# WireTest.net
KiCad netlist of a schematic drawn in Altium Designer
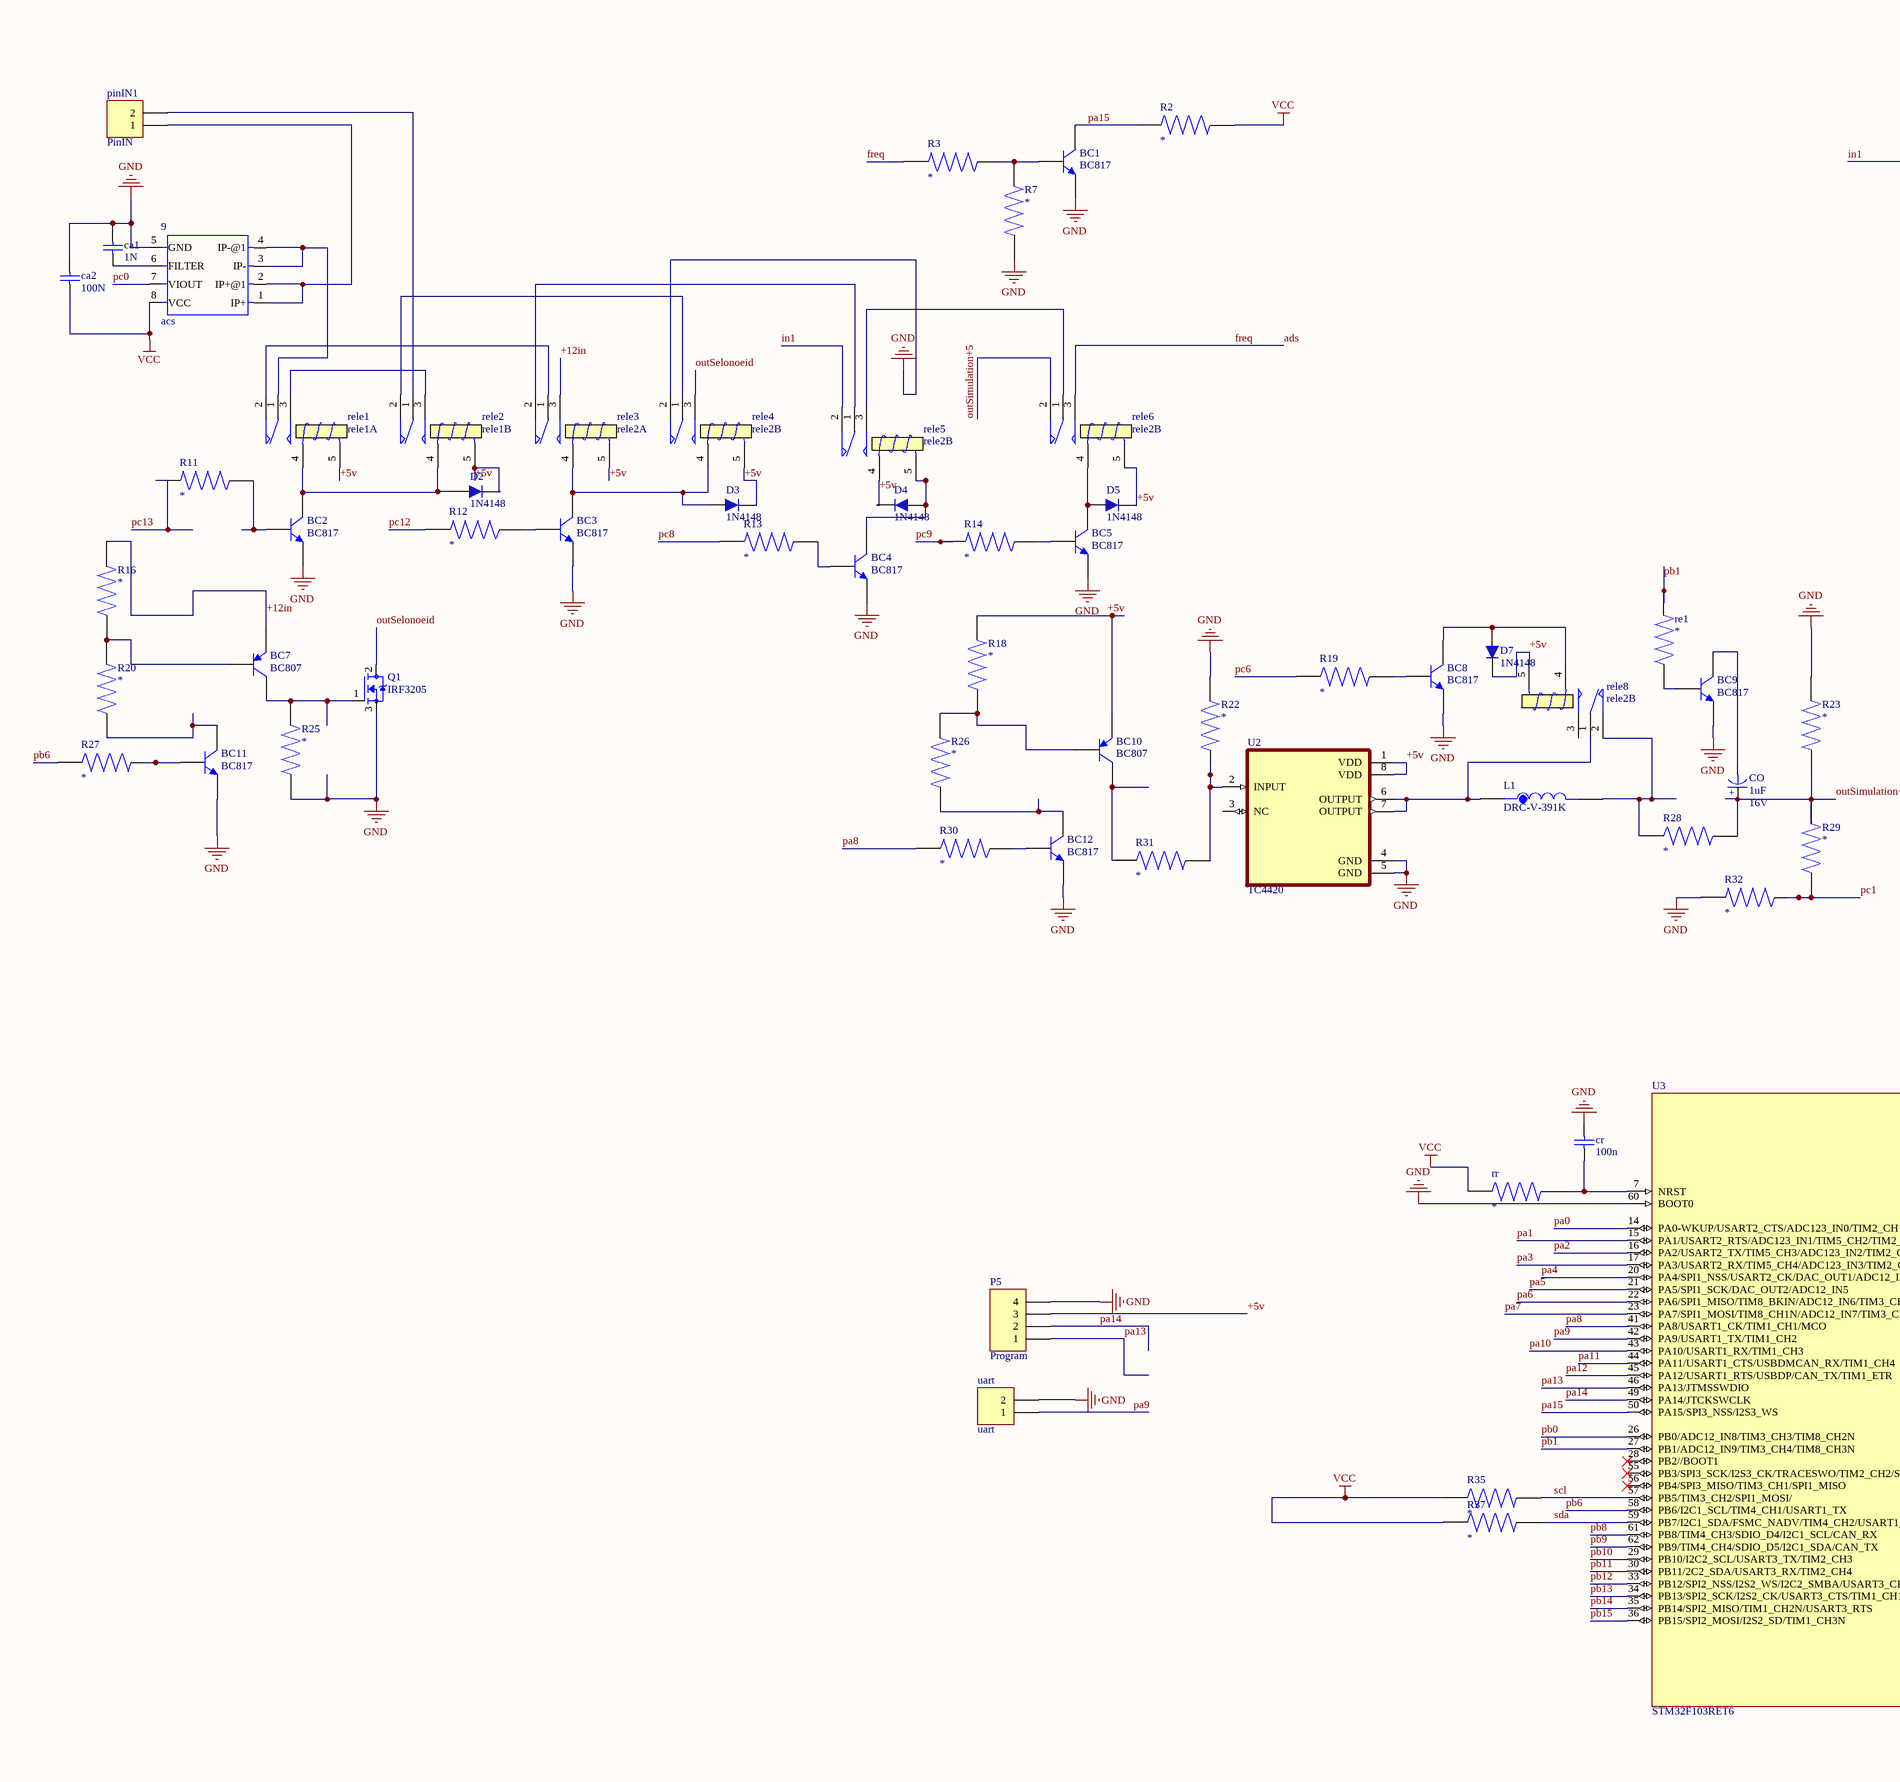
[diagram p0: WireTest.SchDoc, left]
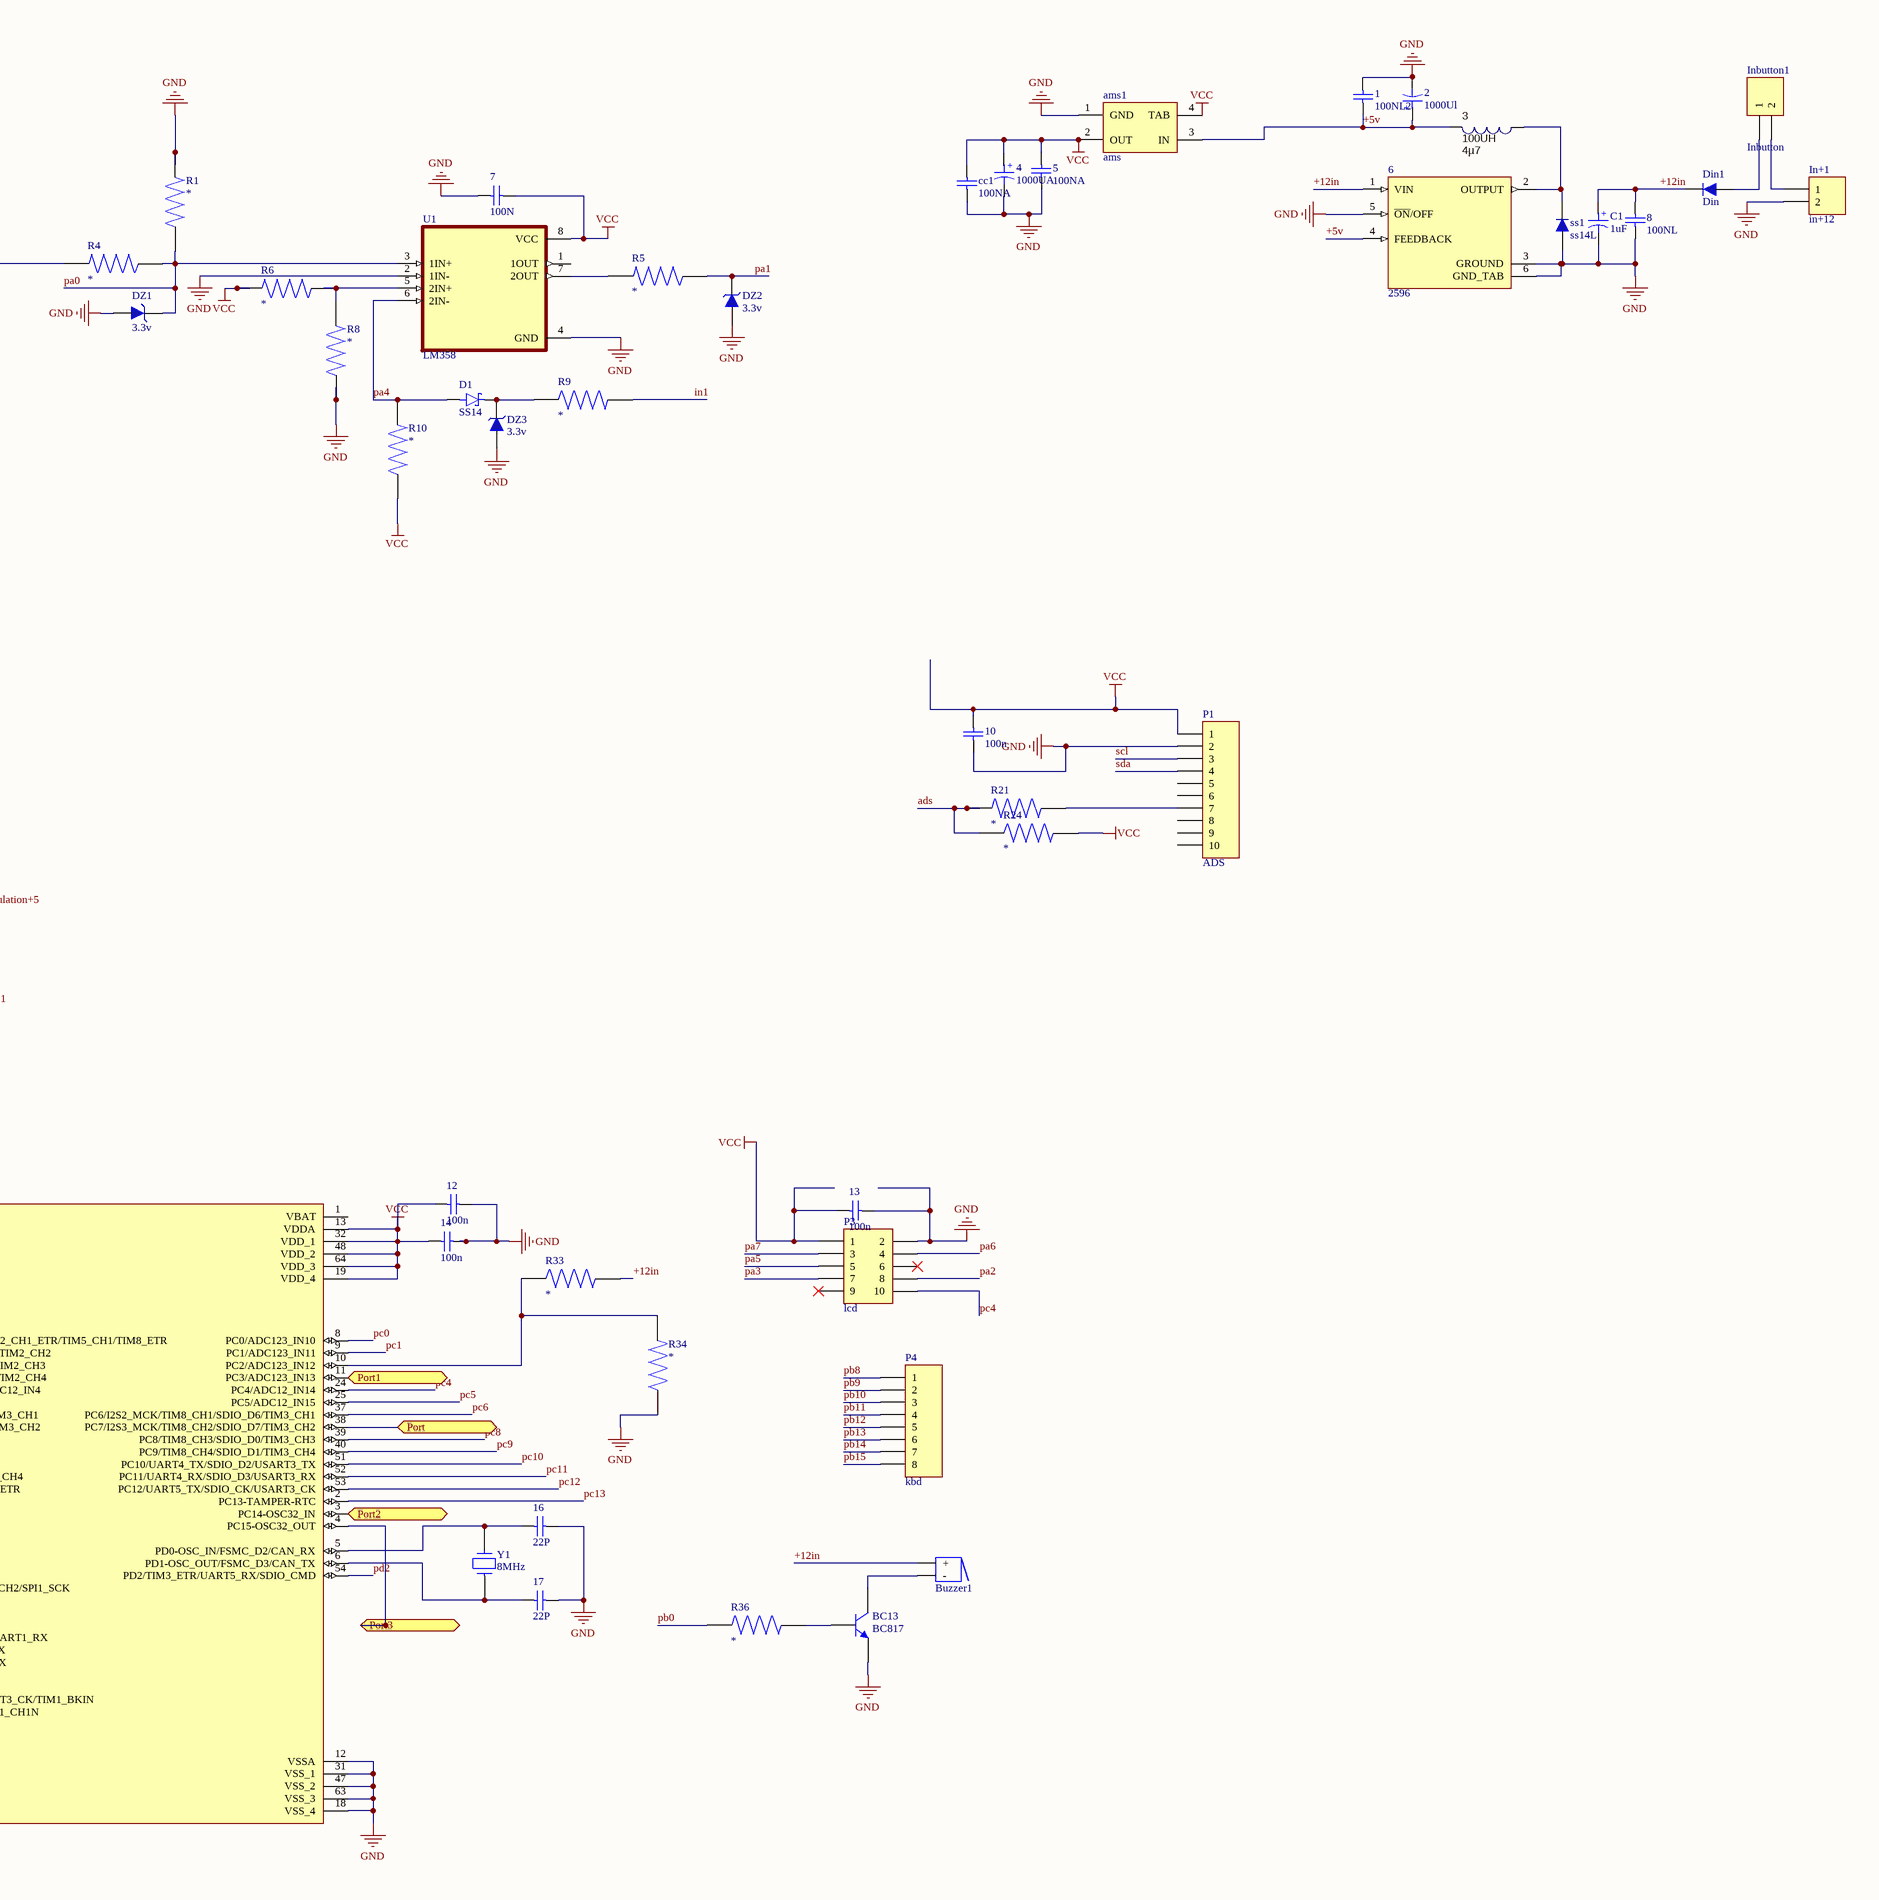
[diagram p1: WireTest.SchDoc, right]

(export (version "E")
  (design (tool "Eeschema 10.0.6"))
  (components
    (comp (ref "1")
      (value "100NL2")
      (footprint "CAPC3413X12N")
      (description "CAP 0805")
      (fields (field (name "DESIGNER") "Abbas Basereh"))
      (libsource (lib "Altium") (part "CAP SMD 0805"))
    )
    (comp (ref "2")
      (value "1000Ul")
      (footprint "Cap electrolitic radial 8x12-3.5")
      (description "Cap electrolitic radial")
      (fields (field (name "DESIGNER") "Abbas Basereh"))
      (libsource (lib "Altium") (part "Cap ELECTROLITIC TOTAL SIZE"))
    )
    (comp (ref "3")
      (value "100UH")
      (footprint "Inductor SMD 3x3.2mm")
      (description "Inductor 4.7µH SMD 3x3.2mm")
      (fields (field (name "TOLERANCE") "±20%") (field (name "ALTIUM_VALUE") "4µ7"))
      (libsource (lib "Altium") (part "Inductor 4.7µH SMD 3x3.2mm"))
    )
    (comp (ref "4")
      (value "1000UA")
      (footprint "Cap electrolitic radial 8x12-3.5")
      (description "Cap electrolitic radial")
      (fields (field (name "DESIGNER") "Abbas Basereh"))
      (libsource (lib "Altium") (part "Cap ELECTROLITIC TOTAL SIZE"))
    )
    (comp (ref "5")
      (value "100NA")
      (footprint "CAPC3413X12N")
      (description "CAP 0805")
      (fields (field (name "DESIGNER") "Abbas Basereh"))
      (libsource (lib "Altium") (part "CAP SMD 0805"))
    )
    (comp (ref "6")
      (value "2596")
      (footprint "LM2596S-5.0:TO170P1524X483-6N")
      (fields (field (name "MP") "LM2596S-5.0"))
      (libsource (lib "LM2596S-5.0") (part "LM2596S-5.0"))
    )
    (comp (ref "7")
      (value "100N")
      (footprint "CAPC3413X12N")
      (description "CAP 0805")
      (fields (field (name "DESIGNER") "Abbas Basereh"))
      (libsource (lib "Altium") (part "CAP SMD 0805"))
    )
    (comp (ref "8")
      (value "100NL")
      (footprint "CAPC3413X12N")
      (description "CAP 0805")
      (fields (field (name "DESIGNER") "Abbas Basereh"))
      (libsource (lib "Altium") (part "CAP SMD 0805"))
    )
    (comp (ref "9")
      (value "acs")
      (footprint "SOIC8-1.27-5X4MM")
      (description "Current Sensor 5A 1 Channel Hall Effect, Open Loop Bidirectional 8-SOIC _0.154, 3.90mm Width_")
      (fields (field (name "MF") "Allegro") (field (name "MP") "ACS712ELCTR-05B-T"))
      (libsource (lib "CURRENT-ACS712ELCTR-05B-T_SOIC8-5X4MM_") (part "CURRENT-ACS712ELCTR-05B-T(SOIC8-5X4MM)"))
    )
    (comp (ref "10")
      (value "100n")
      (footprint "CAPC3413X12N")
      (description "CAP 0805")
      (fields (field (name "DESIGNER") "Abbas Basereh"))
      (libsource (lib "Altium") (part "CAP SMD 0805"))
    )
    (comp (ref "12")
      (value "100n")
      (footprint "CAPC3413X12N")
      (description "CAP 0805")
      (fields (field (name "DESIGNER") "Abbas Basereh"))
      (libsource (lib "Altium") (part "CAP SMD 0805"))
    )
    (comp (ref "13")
      (value "100n")
      (footprint "CAPC3413X12N")
      (description "CAP 0805")
      (fields (field (name "DESIGNER") "Abbas Basereh"))
      (libsource (lib "Altium") (part "CAP SMD 0805"))
    )
    (comp (ref "14")
      (value "100n")
      (footprint "CAPC3413X12N")
      (description "CAP 0805")
      (fields (field (name "DESIGNER") "Abbas Basereh"))
      (libsource (lib "Altium") (part "CAP SMD 0805"))
    )
    (comp (ref "16")
      (value "22P")
      (footprint "CAPC3413X12N")
      (description "CAP 0805")
      (fields (field (name "DESIGNER") "Abbas Basereh"))
      (libsource (lib "Altium") (part "CAP SMD 0805"))
    )
    (comp (ref "17")
      (value "22P")
      (footprint "CAPC3413X12N")
      (description "CAP 0805")
      (fields (field (name "DESIGNER") "Abbas Basereh"))
      (libsource (lib "Altium") (part "CAP SMD 0805"))
    )
    (comp (ref "ams1")
      (value "ams")
      (footprint "MP04A_N")
      (description "x.x Volt, 800mA Low-Dropout Linear Regulator, 4-pin SOT-223")
      (fields
        (field (name "PARTNUMBER") "LM1117IMP-3.3")
        (field (name "MANUFACTURER") "National Semiconductor")
        (field (name "PUBLISHER") "Altium Limited")
      )
      (libsource (lib "My_Library") (part "LM1117IMP-x.x"))
    )
    (comp (ref "BC1")
      (value "BC817")
      (footprint "SOT23_N")
      (description "45 V, 500 mA NPN general-purpose transistors")
      (fields (field (name "PUBLISHER") "Abbas Basereh"))
      (libsource (lib "Altium") (part "BC817"))
    )
    (comp (ref "BC2")
      (value "BC817")
      (footprint "SOT23_N")
      (description "45 V, 500 mA NPN general-purpose transistors")
      (fields (field (name "PUBLISHER") "Abbas Basereh"))
      (libsource (lib "Altium") (part "BC817"))
    )
    (comp (ref "BC3")
      (value "BC817")
      (footprint "SOT23_N")
      (description "45 V, 500 mA NPN general-purpose transistors")
      (fields (field (name "PUBLISHER") "Abbas Basereh"))
      (libsource (lib "Altium") (part "BC817"))
    )
    (comp (ref "BC4")
      (value "BC817")
      (footprint "SOT23_N")
      (description "45 V, 500 mA NPN general-purpose transistors")
      (fields (field (name "PUBLISHER") "Abbas Basereh"))
      (libsource (lib "Altium") (part "BC817"))
    )
    (comp (ref "BC5")
      (value "BC817")
      (footprint "SOT23_N")
      (description "45 V, 500 mA NPN general-purpose transistors")
      (fields (field (name "PUBLISHER") "Abbas Basereh"))
      (libsource (lib "Altium") (part "BC817"))
    )
    (comp (ref "BC7")
      (value "BC807")
      (footprint "SOT23_BEC_N")
      (description "PNP General-purpose Transistor")
      (fields (field (name "PUBLISHER") "Altium Limited"))
      (libsource (lib "Altium") (part "BC807"))
    )
    (comp (ref "BC8")
      (value "BC817")
      (footprint "SOT23_N")
      (description "45 V, 500 mA NPN general-purpose transistors")
      (fields (field (name "PUBLISHER") "Abbas Basereh"))
      (libsource (lib "Altium") (part "BC817"))
    )
    (comp (ref "BC9")
      (value "BC817")
      (footprint "SOT23_N")
      (description "45 V, 500 mA NPN general-purpose transistors")
      (fields (field (name "PUBLISHER") "Abbas Basereh"))
      (libsource (lib "Altium") (part "BC817"))
    )
    (comp (ref "BC10")
      (value "BC807")
      (footprint "SOT23_BEC_N")
      (description "PNP General-purpose Transistor")
      (fields (field (name "PUBLISHER") "Altium Limited"))
      (libsource (lib "Altium") (part "BC807"))
    )
    (comp (ref "BC11")
      (value "BC817")
      (footprint "SOT23_N")
      (description "45 V, 500 mA NPN general-purpose transistors")
      (fields (field (name "PUBLISHER") "Abbas Basereh"))
      (libsource (lib "Altium") (part "BC817"))
    )
    (comp (ref "BC12")
      (value "BC817")
      (footprint "SOT23_N")
      (description "45 V, 500 mA NPN general-purpose transistors")
      (fields (field (name "PUBLISHER") "Abbas Basereh"))
      (libsource (lib "Altium") (part "BC817"))
    )
    (comp (ref "BC13")
      (value "BC817")
      (footprint "SOT23_N")
      (description "45 V, 500 mA NPN general-purpose transistors")
      (fields (field (name "PUBLISHER") "Abbas Basereh"))
      (libsource (lib "Altium") (part "BC817"))
    )
    (comp (ref "Buzzer1")
      (value "Buzzer")
      (footprint "BUZZER")
      (fields (field (name "DESIGNER") "Seyed Mohsen Ghasemain"))
      (libsource (lib "usefully_Library") (part "Buzzer"))
    )
    (comp (ref "C1")
      (value "1uF")
      (footprint "Cap electrolitic radial 8x12-3.5")
      (description "Cap electrolitic radial")
      (fields (field (name "DESIGNER") "Abbas Basereh"))
      (libsource (lib "Altium") (part "Cap ELECTROLITIC TOTAL SIZE"))
    )
    (comp (ref "ca1")
      (value "1N")
      (footprint "CAPC3413X12N")
      (description "CAP 0805")
      (fields (field (name "DESIGNER") "Abbas Basereh"))
      (libsource (lib "Altium") (part "CAP SMD 0805"))
    )
    (comp (ref "ca2")
      (value "100N")
      (footprint "CAPC3413X12N")
      (description "CAP 0805")
      (fields (field (name "DESIGNER") "Abbas Basereh"))
      (libsource (lib "Altium") (part "CAP SMD 0805"))
    )
    (comp (ref "cc1")
      (value "100NA")
      (footprint "CAPC3413X12N")
      (description "CAP 0805")
      (fields (field (name "DESIGNER") "Abbas Basereh"))
      (libsource (lib "Altium") (part "CAP SMD 0805"))
    )
    (comp (ref "CO")
      (value "1uF")
      (footprint "cap 01")
      (description "Polar Capacitor")
      (fields
        (field (name "VOLTAGE") "16V")
        (field (name "Comment") "400U")
        (field (name "DESIGNER") "Saeid Jorablo")
      )
      (libsource (lib "My_Library") (part "Cap-Polar"))
    )
    (comp (ref "cr")
      (value "100n")
      (footprint "CAPC3413X12N")
      (description "CAP 0805")
      (fields (field (name "DESIGNER") "Abbas Basereh"))
      (libsource (lib "Altium") (part "CAP SMD 0805"))
    )
    (comp (ref "D1") (value "SS14") (footprint "DIOM4325X250N") (libsource (lib "SS14") (part "SS14")))
    (comp (ref "D2")
      (value "1N4148")
      (footprint "Diode 1n4148 SMD")
      (description "General Semicoductor")
      (libsource (lib "Altium") (part "1N4148 SMD"))
    )
    (comp (ref "D3")
      (value "1N4148")
      (footprint "Diode 1n4148 SMD")
      (description "General Semicoductor")
      (libsource (lib "Altium") (part "1N4148 SMD"))
    )
    (comp (ref "D4")
      (value "1N4148")
      (footprint "Diode 1n4148 SMD")
      (description "General Semicoductor")
      (libsource (lib "Altium") (part "1N4148 SMD"))
    )
    (comp (ref "D5")
      (value "1N4148")
      (footprint "Diode 1n4148 SMD")
      (description "General Semicoductor")
      (libsource (lib "Altium") (part "1N4148 SMD"))
    )
    (comp (ref "D7")
      (value "1N4148")
      (footprint "Diode 1n4148 SMD")
      (description "General Semicoductor")
      (libsource (lib "Altium") (part "1N4148 SMD"))
    )
    (comp (ref "Din1")
      (value "Din")
      (footprint "Diode 1W Stand")
      (description "Diode DIP Package")
      (fields (field (name "PUBLISHER") "Altium Limited"))
      (libsource (lib "Altium") (part "Diode DIP Package"))
    )
    (comp (ref "DZ1")
      (value "3.3v")
      (footprint "SOD80, LL-34")
      (description "DIODE ZENER GENERAL")
      (fields (field (name "PUBLISHER") "Abbas Basereh"))
      (libsource (lib "Altium") (part "ZENER GENERAL DIODE"))
    )
    (comp (ref "DZ2")
      (value "3.3v")
      (footprint "SOD80, LL-34")
      (description "DIODE ZENER GENERAL")
      (fields (field (name "PUBLISHER") "Abbas Basereh"))
      (libsource (lib "Altium") (part "ZENER GENERAL DIODE"))
    )
    (comp (ref "DZ3")
      (value "3.3v")
      (footprint "SOD80, LL-34")
      (description "DIODE ZENER GENERAL")
      (fields (field (name "PUBLISHER") "Abbas Basereh"))
      (libsource (lib "Altium") (part "ZENER GENERAL DIODE"))
    )
    (comp (ref "In+1")
      (value "in+12")
      (footprint "HDR1X2")
      (description "Header, 2-Pin")
      (fields (field (name "PUBLISHER") "Altium Limited"))
      (libsource (lib "") (part "Header 2_2"))
    )
    (comp (ref "Inbutton1")
      (value "Inbutton")
      (footprint "HDR1X2")
      (description "Header, 2-Pin")
      (fields (field (name "PUBLISHER") "Altium Limited"))
      (libsource (lib "") (part "Header 2_1"))
    )
    (comp (ref "L1")
      (value "DRC-V-391K")
      (footprint "IND_DRC-V-391K")
      (description "Radial Coil Inductor")
      (fields (field (name "MF") "Bel Fuse"))
      (libsource (lib "DRC-V-391K") (part "DRC-V-391K"))
    )
    (comp (ref "P1")
      (value "ADS")
      (footprint "HDR1X10")
      (description "Header, 10-Pin")
      (fields (field (name "PUBLISHER") "Altium Limited"))
      (libsource (lib "Miscellaneous Connectors") (part "Header 10"))
    )
    (comp (ref "P3")
      (value "lcd")
      (footprint "HDR2X5")
      (description "Header, 5-Pin, Dual row")
      (fields (field (name "PUBLISHER") "Altium Limited"))
      (libsource (lib "Miscellaneous Connectors") (part "Header 5X2"))
    )
    (comp (ref "P4")
      (value "kbd")
      (footprint "HDR1X8")
      (description "Header, 8-Pin")
      (fields (field (name "PUBLISHER") "Altium Limited"))
      (libsource (lib "Miscellaneous Connectors") (part "Header 8"))
    )
    (comp (ref "P5")
      (value "Program")
      (footprint "HDR1X4")
      (description "Header, 4-Pin")
      (fields (field (name "PUBLISHER") "Altium Limited"))
      (libsource (lib "Miscellaneous Connectors") (part "Header 4"))
    )
    (comp (ref "pinIN1")
      (value "PinIN")
      (footprint "HDR1X2")
      (description "Header, 2-Pin")
      (fields (field (name "PUBLISHER") "Altium Limited"))
      (libsource (lib "Miscellaneous Connectors") (part "Header 2"))
    )
    (comp (ref "Q1")
      (value "IRF3205")
      (footprint "TO254P1067X483X3124-3P")
      (description "N-Channel 55V 110A _Tc_ 200W _Tc_ Through Hole TO-220AB")
      (fields (field (name "MP") "IRF3205PBF") (field (name "MF") "Infineon Technologies"))
      (libsource (lib "IRF3205PBF") (part "IRF3205PBF"))
    )
    (comp (ref "R1")
      (value "4.7k")
      (footprint "RESC2012X65N")
      (fields
        (field (name "MF") "TE Connectivity")
        (field (name "MP") "CRGCQ0805F10K")
        (field (name "COMMENT_1") "*")
      )
      (libsource (lib "CRGCQ0805F10K") (part "CRGCQ0805F10K"))
    )
    (comp (ref "R2")
      (value "10k")
      (footprint "RESC2012X65N")
      (fields
        (field (name "MF") "TE Connectivity")
        (field (name "MP") "CRGCQ0805F10K")
        (field (name "COMMENT_1") "*")
      )
      (libsource (lib "CRGCQ0805F10K") (part "CRGCQ0805F10K"))
    )
    (comp (ref "R3")
      (value "4.7k")
      (footprint "RESC2012X65N")
      (fields
        (field (name "MF") "TE Connectivity")
        (field (name "MP") "CRGCQ0805F10K")
        (field (name "COMMENT_1") "*")
      )
      (libsource (lib "CRGCQ0805F10K") (part "CRGCQ0805F10K"))
    )
    (comp (ref "R4")
      (value "47k")
      (footprint "RESC2012X65N")
      (fields
        (field (name "MF") "TE Connectivity")
        (field (name "MP") "CRGCQ0805F10K")
        (field (name "COMMENT_1") "*")
      )
      (libsource (lib "CRGCQ0805F10K") (part "CRGCQ0805F10K"))
    )
    (comp (ref "R5")
      (value "1k")
      (footprint "RESC2012X65N")
      (fields
        (field (name "MF") "TE Connectivity")
        (field (name "MP") "CRGCQ0805F10K")
        (field (name "COMMENT_1") "*")
      )
      (libsource (lib "CRGCQ0805F10K") (part "CRGCQ0805F10K"))
    )
    (comp (ref "R6")
      (value "4.7k")
      (footprint "RESC2012X65N")
      (fields
        (field (name "MF") "TE Connectivity")
        (field (name "MP") "CRGCQ0805F10K")
        (field (name "COMMENT_1") "*")
      )
      (libsource (lib "CRGCQ0805F10K") (part "CRGCQ0805F10K"))
    )
    (comp (ref "R7")
      (value "10k")
      (footprint "RESC2012X65N")
      (fields
        (field (name "MF") "TE Connectivity")
        (field (name "MP") "CRGCQ0805F10K")
        (field (name "COMMENT_1") "*")
      )
      (libsource (lib "CRGCQ0805F10K") (part "CRGCQ0805F10K"))
    )
    (comp (ref "R8")
      (value "2.2k")
      (footprint "RESC2012X65N")
      (fields
        (field (name "MF") "TE Connectivity")
        (field (name "MP") "CRGCQ0805F10K")
        (field (name "COMMENT_1") "*")
      )
      (libsource (lib "CRGCQ0805F10K") (part "CRGCQ0805F10K"))
    )
    (comp (ref "R9")
      (value "4.7k")
      (footprint "RESC2012X65N")
      (fields
        (field (name "MF") "TE Connectivity")
        (field (name "MP") "CRGCQ0805F10K")
        (field (name "COMMENT_1") "*")
      )
      (libsource (lib "CRGCQ0805F10K") (part "CRGCQ0805F10K"))
    )
    (comp (ref "R10")
      (value "10k")
      (footprint "RESC2012X65N")
      (fields
        (field (name "MF") "TE Connectivity")
        (field (name "MP") "CRGCQ0805F10K")
        (field (name "COMMENT_1") "*")
      )
      (libsource (lib "CRGCQ0805F10K") (part "CRGCQ0805F10K"))
    )
    (comp (ref "R11")
      (value "1k")
      (footprint "RESC2012X65N")
      (fields
        (field (name "MF") "TE Connectivity")
        (field (name "MP") "CRGCQ0805F10K")
        (field (name "COMMENT_1") "*")
      )
      (libsource (lib "CRGCQ0805F10K") (part "CRGCQ0805F10K"))
    )
    (comp (ref "R12")
      (value "1k")
      (footprint "RESC2012X65N")
      (fields
        (field (name "MF") "TE Connectivity")
        (field (name "MP") "CRGCQ0805F10K")
        (field (name "COMMENT_1") "*")
      )
      (libsource (lib "CRGCQ0805F10K") (part "CRGCQ0805F10K"))
    )
    (comp (ref "R13")
      (value "1k")
      (footprint "RESC2012X65N")
      (fields
        (field (name "MF") "TE Connectivity")
        (field (name "MP") "CRGCQ0805F10K")
        (field (name "COMMENT_1") "*")
      )
      (libsource (lib "CRGCQ0805F10K") (part "CRGCQ0805F10K"))
    )
    (comp (ref "R14")
      (value "1k")
      (footprint "RESC2012X65N")
      (fields
        (field (name "MF") "TE Connectivity")
        (field (name "MP") "CRGCQ0805F10K")
        (field (name "COMMENT_1") "*")
      )
      (libsource (lib "CRGCQ0805F10K") (part "CRGCQ0805F10K"))
    )
    (comp (ref "R16")
      (value "10k")
      (footprint "RESC2012X65N")
      (fields
        (field (name "MF") "TE Connectivity")
        (field (name "MP") "CRGCQ0805F10K")
        (field (name "COMMENT_1") "*")
      )
      (libsource (lib "CRGCQ0805F10K") (part "CRGCQ0805F10K"))
    )
    (comp (ref "R18")
      (value "4.7k")
      (footprint "RESC2012X65N")
      (fields
        (field (name "MF") "TE Connectivity")
        (field (name "MP") "CRGCQ0805F10K")
        (field (name "COMMENT_1") "*")
      )
      (libsource (lib "CRGCQ0805F10K") (part "CRGCQ0805F10K"))
    )
    (comp (ref "R19")
      (value "1k")
      (footprint "RESC2012X65N")
      (fields
        (field (name "MF") "TE Connectivity")
        (field (name "MP") "CRGCQ0805F10K")
        (field (name "COMMENT_1") "*")
      )
      (libsource (lib "CRGCQ0805F10K") (part "CRGCQ0805F10K"))
    )
    (comp (ref "R20")
      (value "4.7k")
      (footprint "RESC2012X65N")
      (fields
        (field (name "MF") "TE Connectivity")
        (field (name "MP") "CRGCQ0805F10K")
        (field (name "COMMENT_1") "*")
      )
      (libsource (lib "CRGCQ0805F10K") (part "CRGCQ0805F10K"))
    )
    (comp (ref "R21")
      (value "10k")
      (footprint "RESC2012X65N")
      (fields
        (field (name "MF") "TE Connectivity")
        (field (name "MP") "CRGCQ0805F10K")
        (field (name "COMMENT_1") "*")
      )
      (libsource (lib "CRGCQ0805F10K") (part "CRGCQ0805F10K"))
    )
    (comp (ref "R22")
      (value "2.2k")
      (footprint "RESC2012X65N")
      (fields
        (field (name "MF") "TE Connectivity")
        (field (name "MP") "CRGCQ0805F10K")
        (field (name "COMMENT_1") "*")
      )
      (libsource (lib "CRGCQ0805F10K") (part "CRGCQ0805F10K"))
    )
    (comp (ref "R23")
      (value "adj")
      (footprint "RESC2012X65N")
      (fields
        (field (name "MF") "TE Connectivity")
        (field (name "MP") "CRGCQ0805F10K")
        (field (name "COMMENT_1") "*")
      )
      (libsource (lib "CRGCQ0805F10K") (part "CRGCQ0805F10K"))
    )
    (comp (ref "R24")
      (value "10k")
      (footprint "RESC2012X65N")
      (fields
        (field (name "MF") "TE Connectivity")
        (field (name "MP") "CRGCQ0805F10K")
        (field (name "COMMENT_1") "*")
      )
      (libsource (lib "CRGCQ0805F10K") (part "CRGCQ0805F10K"))
    )
    (comp (ref "R25")
      (value "10k")
      (footprint "RESC2012X65N")
      (fields
        (field (name "MF") "TE Connectivity")
        (field (name "MP") "CRGCQ0805F10K")
        (field (name "COMMENT_1") "*")
      )
      (libsource (lib "CRGCQ0805F10K") (part "CRGCQ0805F10K"))
    )
    (comp (ref "R26")
      (value "1k")
      (footprint "RESC2012X65N")
      (fields
        (field (name "MF") "TE Connectivity")
        (field (name "MP") "CRGCQ0805F10K")
        (field (name "COMMENT_1") "*")
      )
      (libsource (lib "CRGCQ0805F10K") (part "CRGCQ0805F10K"))
    )
    (comp (ref "R27")
      (value "4.7k")
      (footprint "RESC2012X65N")
      (fields
        (field (name "MF") "TE Connectivity")
        (field (name "MP") "CRGCQ0805F10K")
        (field (name "COMMENT_1") "*")
      )
      (libsource (lib "CRGCQ0805F10K") (part "CRGCQ0805F10K"))
    )
    (comp (ref "R28")
      (value "20r")
      (footprint "RESC2012X65N")
      (fields
        (field (name "MF") "TE Connectivity")
        (field (name "MP") "CRGCQ0805F10K")
        (field (name "COMMENT_1") "*")
      )
      (libsource (lib "CRGCQ0805F10K") (part "CRGCQ0805F10K"))
    )
    (comp (ref "R29")
      (value "10k")
      (footprint "RESC2012X65N")
      (fields
        (field (name "MF") "TE Connectivity")
        (field (name "MP") "CRGCQ0805F10K")
        (field (name "COMMENT_1") "*")
      )
      (libsource (lib "CRGCQ0805F10K") (part "CRGCQ0805F10K"))
    )
    (comp (ref "R30")
      (value "330r")
      (footprint "RESC2012X65N")
      (fields
        (field (name "MF") "TE Connectivity")
        (field (name "MP") "CRGCQ0805F10K")
        (field (name "COMMENT_1") "*")
      )
      (libsource (lib "CRGCQ0805F10K") (part "CRGCQ0805F10K"))
    )
    (comp (ref "R31")
      (value "20r")
      (footprint "RESC2012X65N")
      (fields
        (field (name "MF") "TE Connectivity")
        (field (name "MP") "CRGCQ0805F10K")
        (field (name "COMMENT_1") "*")
      )
      (libsource (lib "CRGCQ0805F10K") (part "CRGCQ0805F10K"))
    )
    (comp (ref "R32")
      (value "4.7k")
      (footprint "RESC2012X65N")
      (fields
        (field (name "MF") "TE Connectivity")
        (field (name "MP") "CRGCQ0805F10K")
        (field (name "COMMENT_1") "*")
      )
      (libsource (lib "CRGCQ0805F10K") (part "CRGCQ0805F10K"))
    )
    (comp (ref "R33")
      (value "10k")
      (footprint "RESC2012X65N")
      (fields
        (field (name "MF") "TE Connectivity")
        (field (name "MP") "CRGCQ0805F10K")
        (field (name "COMMENT_1") "*")
      )
      (libsource (lib "CRGCQ0805F10K") (part "CRGCQ0805F10K"))
    )
    (comp (ref "R34")
      (value "1k")
      (footprint "RESC2012X65N")
      (fields
        (field (name "MF") "TE Connectivity")
        (field (name "MP") "CRGCQ0805F10K")
        (field (name "COMMENT_1") "*")
      )
      (libsource (lib "CRGCQ0805F10K") (part "CRGCQ0805F10K"))
    )
    (comp (ref "R35")
      (value "4k7")
      (footprint "RESC2012X65N")
      (fields
        (field (name "MF") "TE Connectivity")
        (field (name "MP") "CRGCQ0805F10K")
        (field (name "COMMENT_1") "*")
      )
      (libsource (lib "CRGCQ0805F10K") (part "CRGCQ0805F10K"))
    )
    (comp (ref "R36")
      (value "1k")
      (footprint "RESC2012X65N")
      (fields
        (field (name "MF") "TE Connectivity")
        (field (name "MP") "CRGCQ0805F10K")
        (field (name "COMMENT_1") "*")
      )
      (libsource (lib "CRGCQ0805F10K") (part "CRGCQ0805F10K"))
    )
    (comp (ref "R37")
      (value "4k7")
      (footprint "RESC2012X65N")
      (fields
        (field (name "MF") "TE Connectivity")
        (field (name "MP") "CRGCQ0805F10K")
        (field (name "COMMENT_1") "*")
      )
      (libsource (lib "CRGCQ0805F10K") (part "CRGCQ0805F10K"))
    )
    (comp (ref "re1")
      (value "1k")
      (footprint "RESC2012X65N")
      (fields
        (field (name "MF") "TE Connectivity")
        (field (name "MP") "CRGCQ0805F10K")
        (field (name "COMMENT_1") "*")
      )
      (libsource (lib "CRGCQ0805F10K") (part "CRGCQ0805F10K"))
    )
    (comp (ref "rele1")
      (value "rele1A")
      (footprint "Relay 15.40x12.10x13.10")
      (description "Relay_SPDT POWER NEEDLE")
      (fields (field (name "DESIGNER") "Ali Hafizi"))
      (libsource (lib "") (part "RELAY General_1"))
    )
    (comp (ref "rele2")
      (value "rele1B")
      (footprint "Relay 15.40x12.10x13.10")
      (description "Relay_SPDT POWER NEEDLE")
      (fields (field (name "DESIGNER") "Ali Hafizi"))
      (libsource (lib "") (part "RELAY General_1"))
    )
    (comp (ref "rele3")
      (value "rele2A")
      (footprint "Relay 15.40x12.10x13.10")
      (description "Relay_SPDT POWER NEEDLE")
      (fields (field (name "DESIGNER") "Ali Hafizi"))
      (libsource (lib "") (part "RELAY General_1"))
    )
    (comp (ref "rele4")
      (value "rele2B")
      (footprint "Relay 15.40x12.10x13.10")
      (description "Relay_SPDT POWER NEEDLE")
      (fields (field (name "DESIGNER") "Ali Hafizi"))
      (libsource (lib "") (part "RELAY General_1"))
    )
    (comp (ref "rele5")
      (value "rele2B")
      (footprint "Relay 15.40x12.10x13.10")
      (description "Relay_SPDT POWER NEEDLE")
      (fields (field (name "DESIGNER") "Ali Hafizi"))
      (libsource (lib "") (part "RELAY General_1"))
    )
    (comp (ref "rele6")
      (value "rele2B")
      (footprint "Relay 15.40x12.10x13.10")
      (description "Relay_SPDT POWER NEEDLE")
      (fields (field (name "DESIGNER") "Ali Hafizi"))
      (libsource (lib "") (part "RELAY General_1"))
    )
    (comp (ref "rele8")
      (value "rele2B")
      (footprint "Relay 15.40x12.10x13.10")
      (description "Relay_SPDT POWER NEEDLE")
      (fields (field (name "DESIGNER") "Ali Hafizi"))
      (libsource (lib "Altium") (part "RELAY General"))
    )
    (comp (ref "rr")
      (value "1k")
      (footprint "RESC2012X65N")
      (fields
        (field (name "MF") "TE Connectivity")
        (field (name "MP") "CRGCQ0805F10K")
        (field (name "COMMENT_1") "*")
      )
      (libsource (lib "CRGCQ0805F10K") (part "CRGCQ0805F10K"))
    )
    (comp (ref "ss1")
      (value "ss14L")
      (footprint "Diode 1N4007 SMD")
      (description "Diode DIP Package")
      (fields (field (name "PUBLISHER") "Altium Limited"))
      (libsource (lib "Altium") (part "Diode DIP Package"))
    )
    (comp (ref "U1")
      (value "LM358")
      (footprint "SOIC127P599X175-8N")
      (description "Dual, 30-V, 700-kHz operational amplifier")
      (fields (field (name "MF") "Texas Instruments") (field (name "MP") "LM358DRG3"))
      (libsource (lib "LM358DRG3") (part "LM358DRG3"))
    )
    (comp (ref "U2")
      (value "TC4420")
      (footprint "DIP787W46P254L927H533Q8")
      (fields (field (name "MF") "Microchip") (field (name "MP") "TC4420CPA"))
      (libsource (lib "TC4420CPA") (part "TC4420CPA"))
    )
    (comp (ref "U3")
      (value "STM32F103RET6")
      (footprint "QFP50P1200X1200X160-64N")
      (description "ARMÂ® CortexÂ®-M3 STM32F1 Microcontroller IC 32-Bit 72MHz 512KB (512K x 8) FLASH 64-LQFP (10x10)")
      (fields (field (name "MF") "STMicroelectronics"))
      (libsource (lib "STM32F103RET6") (part "STM32F103RET6"))
    )
    (comp (ref "uart")
      (value "uart")
      (footprint "HDR1X2")
      (description "Header, 2-Pin")
      (fields (field (name "PUBLISHER") "Altium Limited"))
      (libsource (lib "Miscellaneous Connectors") (part "Header 2"))
    )
    (comp (ref "Y1")
      (value "8MHz")
      (footprint "My_Crystal")
      (description "Crystal")
      (libsource (lib "Devices") (part "CRYSTAL"))
    )
  )
  (nets
    (net (code "1") (name "/+5v") (class "Default")
      (node (ref "1") (pin "1") (pinfunction "1_1") (pintype "passive"))
      (node (ref "2") (pin "1") (pinfunction "1_1") (pintype "passive"))
      (node (ref "3") (pin "2") (pinfunction "2_2") (pintype "passive"))
      (node (ref "6") (pin "4") (pinfunction "FEEDBACK_4") (pintype "input"))
      (node (ref "BC10") (pin "2") (pinfunction "E_2") (pintype "passive"))
      (node (ref "D2") (pin "2") (pintype "passive"))
      (node (ref "D3") (pin "2") (pintype "passive"))
      (node (ref "D4") (pin "2") (pintype "passive"))
      (node (ref "D5") (pin "2") (pintype "passive"))
      (node (ref "D7") (pin "2") (pintype "passive"))
      (node (ref "P5") (pin "3") (pinfunction "3_3") (pintype "passive"))
      (node (ref "R18") (pin "1") (pinfunction "1_1") (pintype "passive"))
      (node (ref "U2") (pin "1") (pinfunction "VDD_1") (pintype "power_in"))
      (node (ref "U2") (pin "8") (pinfunction "VDD_8") (pintype "power_in"))
      (node (ref "ams1") (pin "3") (pinfunction "IN_3") (pintype "power_in"))
      (node (ref "rele1") (pin "5") (pinfunction "T2_5") (pintype "passive"))
      (node (ref "rele2") (pin "5") (pinfunction "T2_5") (pintype "passive"))
      (node (ref "rele3") (pin "5") (pinfunction "T2_5") (pintype "passive"))
      (node (ref "rele4") (pin "5") (pinfunction "T2_5") (pintype "passive"))
      (node (ref "rele5") (pin "4") (pinfunction "T1_4") (pintype "passive"))
      (node (ref "rele6") (pin "5") (pinfunction "T2_5") (pintype "passive"))
      (node (ref "rele8") (pin "5") (pinfunction "T2_5") (pintype "passive"))
    )
    (net (code "2") (name "/+12in") (class "Default")
      (node (ref "6") (pin "1") (pinfunction "VIN_1") (pintype "input"))
      (node (ref "8") (pin "2") (pinfunction "2_2") (pintype "passive"))
      (node (ref "BC7") (pin "2") (pinfunction "E_2") (pintype "passive"))
      (node (ref "Buzzer1") (pin "1") (pinfunction "+_1") (pintype "passive"))
      (node (ref "C1") (pin "1") (pinfunction "1_1") (pintype "passive"))
      (node (ref "Din1") (pin "2") (pintype "passive"))
      (node (ref "R16") (pin "2") (pinfunction "2_2") (pintype "passive"))
      (node (ref "R33") (pin "2") (pinfunction "2_2") (pintype "passive"))
      (node (ref "rele3") (pin "3") (pinfunction "NO_3") (pintype "passive"))
    )
    (net (code "3") (name "/Port") (class "Default")
      (node (ref "U3") (pin "38") (pinfunction "PC7/I2S3_MCK/TIM8_CH2/SDIO_D7/TIM3_CH2_38") (pintype "bidirectional"))
    )
    (net (code "4") (name "/Port1") (class "Default")
      (node (ref "U3") (pin "11") (pinfunction "PC3/ADC123_IN13_11") (pintype "bidirectional"))
    )
    (net (code "5") (name "/Port2") (class "Default")
      (node (ref "U3") (pin "3") (pinfunction "PC14-OSC32_IN_3") (pintype "bidirectional"))
    )
    (net (code "6") (name "/Port3") (class "Default")
      (node (ref "U3") (pin "4") (pinfunction "PC15-OSC32_OUT_4") (pintype "bidirectional"))
    )
    (net (code "7") (name "/ads") (class "Default")
      (node (ref "R21") (pin "1") (pinfunction "1_1") (pintype "passive"))
      (node (ref "R24") (pin "1") (pinfunction "1_1") (pintype "passive"))
      (node (ref "R3") (pin "2") (pinfunction "2_2") (pintype "passive"))
      (node (ref "rele6") (pin "3") (pinfunction "NO_3") (pintype "passive"))
    )
    (net (code "8") (name "/in1") (class "Default")
      (node (ref "R4") (pin "2") (pinfunction "2_2") (pintype "passive"))
      (node (ref "R9") (pin "2") (pinfunction "2_2") (pintype "passive"))
      (node (ref "rele5") (pin "2") (pinfunction "NC_2") (pintype "passive"))
    )
    (net (code "9") (name "/outSelonoeid") (class "Default")
      (node (ref "Q1") (pin "2") (pinfunction "D_2") (pintype "passive"))
      (node (ref "rele4") (pin "3") (pinfunction "NO_3") (pintype "passive"))
    )
    (net (code "10") (name "/outSimulation+5") (class "Default")
      (node (ref "CO") (pin "1") (pinfunction "+_1") (pintype "passive"))
      (node (ref "R23") (pin "1") (pinfunction "1_1") (pintype "passive"))
      (node (ref "R28") (pin "2") (pinfunction "2_2") (pintype "passive"))
      (node (ref "R29") (pin "2") (pinfunction "2_2") (pintype "passive"))
      (node (ref "rele6") (pin "2") (pinfunction "NC_2") (pintype "passive"))
    )
    (net (code "11") (name "/pa0") (class "Default")
      (node (ref "DZ1") (pin "2") (pintype "passive"))
      (node (ref "R1") (pin "2") (pinfunction "2_2") (pintype "passive"))
      (node (ref "R4") (pin "1") (pinfunction "1_1") (pintype "passive"))
      (node (ref "U1") (pin "3") (pinfunction "1IN+_3") (pintype "input"))
      (node (ref "U3") (pin "14") (pinfunction "PA0-WKUP/USART2_CTS/ADC123_IN0/TIM2_CH1_ETR/TIM5_CH1/TIM8_ETR_14") (pintype "bidirectional"))
    )
    (net (code "12") (name "/pa1") (class "Default")
      (node (ref "DZ2") (pin "2") (pintype "passive"))
      (node (ref "R5") (pin "1") (pinfunction "1_1") (pintype "passive"))
      (node (ref "U3") (pin "15") (pinfunction "PA1/USART2_RTS/ADC123_IN1/TIM5_CH2/TIM2_CH2_15") (pintype "bidirectional"))
    )
    (net (code "13") (name "/pa2") (class "Default")
      (node (ref "P3") (pin "8") (pinfunction "8_8") (pintype "passive"))
      (node (ref "U3") (pin "16") (pinfunction "PA2/USART2_TX/TIM5_CH3/ADC123_IN2/TIM2_CH3_16") (pintype "bidirectional"))
    )
    (net (code "14") (name "/pa3") (class "Default")
      (node (ref "P3") (pin "7") (pinfunction "7_7") (pintype "passive"))
      (node (ref "U3") (pin "17") (pinfunction "PA3/USART2_RX/TIM5_CH4/ADC123_IN3/TIM2_CH4_17") (pintype "bidirectional"))
    )
    (net (code "15") (name "/pa4") (class "Default")
      (node (ref "D1") (pin "A") (pinfunction "A_A") (pintype "passive"))
      (node (ref "R10") (pin "1") (pinfunction "1_1") (pintype "passive"))
      (node (ref "U1") (pin "6") (pinfunction "2IN-_6") (pintype "input"))
      (node (ref "U3") (pin "20") (pinfunction "PA4/SPI1_NSS/USART2_CK/DAC_OUT1/ADC12_IN4_20") (pintype "bidirectional"))
    )
    (net (code "16") (name "/pa5") (class "Default")
      (node (ref "P3") (pin "5") (pinfunction "5_5") (pintype "passive"))
      (node (ref "U3") (pin "21") (pinfunction "PA5/SPI1_SCK/DAC_OUT2/ADC12_IN5_21") (pintype "bidirectional"))
    )
    (net (code "17") (name "/pa6") (class "Default")
      (node (ref "P3") (pin "4") (pinfunction "4_4") (pintype "passive"))
      (node (ref "U3") (pin "22") (pinfunction "PA6/SPI1_MISO/TIM8_BKIN/ADC12_IN6/TIM3_CH1_22") (pintype "bidirectional"))
    )
    (net (code "18") (name "/pa7") (class "Default")
      (node (ref "P3") (pin "3") (pinfunction "3_3") (pintype "passive"))
      (node (ref "U3") (pin "23") (pinfunction "PA7/SPI1_MOSI/TIM8_CH1N/ADC12_IN7/TIM3_CH2_23") (pintype "bidirectional"))
    )
    (net (code "19") (name "/pa8") (class "Default")
      (node (ref "R30") (pin "2") (pinfunction "2_2") (pintype "passive"))
      (node (ref "U3") (pin "41") (pinfunction "PA8/USART1_CK/TIM1_CH1/MCO_41") (pintype "bidirectional"))
    )
    (net (code "20") (name "/pa9") (class "Default")
      (node (ref "U3") (pin "42") (pinfunction "PA9/USART1_TX/TIM1_CH2_42") (pintype "bidirectional"))
      (node (ref "uart") (pin "1") (pinfunction "1_1") (pintype "passive"))
    )
    (net (code "21") (name "/pa10") (class "Default")
      (node (ref "U3") (pin "43") (pinfunction "PA10/USART1_RX/TIM1_CH3_43") (pintype "bidirectional"))
    )
    (net (code "22") (name "/pa11") (class "Default")
      (node (ref "U3") (pin "44") (pinfunction "PA11/USART1_CTS/USBDMCAN_RX/TIM1_CH4_44") (pintype "bidirectional"))
    )
    (net (code "23") (name "/pa12") (class "Default")
      (node (ref "U3") (pin "45") (pinfunction "PA12/USART1_RTS/USBDP/CAN_TX/TIM1_ETR_45") (pintype "bidirectional"))
    )
    (net (code "24") (name "/pa13") (class "Default")
      (node (ref "P5") (pin "1") (pinfunction "1_1") (pintype "passive"))
      (node (ref "U3") (pin "46") (pinfunction "PA13/JTMSSWDIO_46") (pintype "bidirectional"))
    )
    (net (code "25") (name "/pa14") (class "Default")
      (node (ref "P5") (pin "2") (pinfunction "2_2") (pintype "passive"))
      (node (ref "U3") (pin "49") (pinfunction "PA14/JTCKSWCLK_49") (pintype "bidirectional"))
    )
    (net (code "26") (name "/pa15") (class "Default")
      (node (ref "BC1") (pin "3") (pinfunction "C_3") (pintype "passive"))
      (node (ref "R2") (pin "1") (pinfunction "1_1") (pintype "passive"))
      (node (ref "U3") (pin "50") (pinfunction "PA15/SPI3_NSS/I2S3_WS_50") (pintype "bidirectional"))
    )
    (net (code "27") (name "/pb0") (class "Default")
      (node (ref "R36") (pin "1") (pinfunction "1_1") (pintype "passive"))
      (node (ref "U3") (pin "26") (pinfunction "PB0/ADC12_IN8/TIM3_CH3/TIM8_CH2N_26") (pintype "bidirectional"))
    )
    (net (code "28") (name "/pb1") (class "Default")
      (node (ref "U3") (pin "27") (pinfunction "PB1/ADC12_IN9/TIM3_CH4/TIM8_CH3N_27") (pintype "bidirectional"))
      (node (ref "re1") (pin "2") (pinfunction "2_2") (pintype "passive"))
    )
    (net (code "29") (name "/pb6") (class "Default")
      (node (ref "R27") (pin "1") (pinfunction "1_1") (pintype "passive"))
      (node (ref "U3") (pin "58") (pinfunction "PB6/I2C1_SCL/TIM4_CH1/USART1_TX_58") (pintype "bidirectional"))
    )
    (net (code "30") (name "/pb8") (class "Default")
      (node (ref "P4") (pin "1") (pinfunction "1_1") (pintype "passive"))
      (node (ref "U3") (pin "61") (pinfunction "PB8/TIM4_CH3/SDIO_D4/I2C1_SCL/CAN_RX_61") (pintype "bidirectional"))
    )
    (net (code "31") (name "/pb9") (class "Default")
      (node (ref "P4") (pin "2") (pinfunction "2_2") (pintype "passive"))
      (node (ref "U3") (pin "62") (pinfunction "PB9/TIM4_CH4/SDIO_D5/I2C1_SDA/CAN_TX_62") (pintype "bidirectional"))
    )
    (net (code "32") (name "/pb10") (class "Default")
      (node (ref "P4") (pin "3") (pinfunction "3_3") (pintype "passive"))
      (node (ref "U3") (pin "29") (pinfunction "PB10/I2C2_SCL/USART3_TX/TIM2_CH3_29") (pintype "bidirectional"))
    )
    (net (code "33") (name "/pb11") (class "Default")
      (node (ref "P4") (pin "4") (pinfunction "4_4") (pintype "passive"))
      (node (ref "U3") (pin "30") (pinfunction "PB11/2C2_SDA/USART3_RX/TIM2_CH4_30") (pintype "bidirectional"))
    )
    (net (code "34") (name "/pb12") (class "Default")
      (node (ref "P4") (pin "5") (pinfunction "5_5") (pintype "passive"))
      (node (ref "U3") (pin "33") (pinfunction "PB12/SPI2_NSS/I2S2_WS/I2C2_SMBA/USART3_CK/TIM1_BKIN_33") (pintype "bidirectional"))
    )
    (net (code "35") (name "/pb13") (class "Default")
      (node (ref "P4") (pin "6") (pinfunction "6_6") (pintype "passive"))
      (node (ref "U3") (pin "34") (pinfunction "PB13/SPI2_SCK/I2S2_CK/USART3_CTS/TIM1_CH1N_34") (pintype "bidirectional"))
    )
    (net (code "36") (name "/pb14") (class "Default")
      (node (ref "P4") (pin "7") (pinfunction "7_7") (pintype "passive"))
      (node (ref "U3") (pin "35") (pinfunction "PB14/SPI2_MISO/TIM1_CH2N/USART3_RTS_35") (pintype "bidirectional"))
    )
    (net (code "37") (name "/pb15") (class "Default")
      (node (ref "P4") (pin "8") (pinfunction "8_8") (pintype "passive"))
      (node (ref "U3") (pin "36") (pinfunction "PB15/SPI2_MOSI/I2S2_SD/TIM1_CH3N_36") (pintype "bidirectional"))
    )
    (net (code "38") (name "/pc0") (class "Default")
      (node (ref "9") (pin "7") (pinfunction "VIOUT_7") (pintype "bidirectional"))
      (node (ref "U3") (pin "8") (pinfunction "PC0/ADC123_IN10_8") (pintype "bidirectional"))
    )
    (net (code "39") (name "/pc1") (class "Default")
      (node (ref "R29") (pin "1") (pinfunction "1_1") (pintype "passive"))
      (node (ref "R32") (pin "1") (pinfunction "1_1") (pintype "passive"))
      (node (ref "U3") (pin "9") (pinfunction "PC1/ADC123_IN11_9") (pintype "bidirectional"))
    )
    (net (code "40") (name "/pc4") (class "Default")
      (node (ref "P3") (pin "10") (pinfunction "10_10") (pintype "passive"))
      (node (ref "U3") (pin "24") (pinfunction "PC4/ADC12_IN14_24") (pintype "bidirectional"))
    )
    (net (code "41") (name "/pc5") (class "Default")
      (node (ref "U3") (pin "25") (pinfunction "PC5/ADC12_IN15_25") (pintype "bidirectional"))
    )
    (net (code "42") (name "/pc6") (class "Default")
      (node (ref "R19") (pin "1") (pinfunction "1_1") (pintype "passive"))
      (node (ref "U3") (pin "37") (pinfunction "PC6/I2S2_MCK/TIM8_CH1/SDIO_D6/TIM3_CH1_37") (pintype "bidirectional"))
    )
    (net (code "43") (name "/pc8") (class "Default")
      (node (ref "R13") (pin "2") (pinfunction "2_2") (pintype "passive"))
      (node (ref "U3") (pin "39") (pinfunction "PC8/TIM8_CH3/SDIO_D0/TIM3_CH3_39") (pintype "bidirectional"))
    )
    (net (code "44") (name "/pc9") (class "Default")
      (node (ref "R14") (pin "2") (pinfunction "2_2") (pintype "passive"))
      (node (ref "U3") (pin "40") (pinfunction "PC9/TIM8_CH4/SDIO_D1/TIM3_CH4_40") (pintype "bidirectional"))
    )
    (net (code "45") (name "/pc10") (class "Default")
      (node (ref "U3") (pin "51") (pinfunction "PC10/UART4_TX/SDIO_D2/USART3_TX_51") (pintype "bidirectional"))
    )
    (net (code "46") (name "/pc11") (class "Default")
      (node (ref "U3") (pin "52") (pinfunction "PC11/UART4_RX/SDIO_D3/USART3_RX_52") (pintype "bidirectional"))
    )
    (net (code "47") (name "/pc12") (class "Default")
      (node (ref "R12") (pin "2") (pinfunction "2_2") (pintype "passive"))
      (node (ref "U3") (pin "53") (pinfunction "PC12/UART5_TX/SDIO_CK/USART3_CK_53") (pintype "bidirectional"))
    )
    (net (code "48") (name "/pc13") (class "Default")
      (node (ref "R11") (pin "2") (pinfunction "2_2") (pintype "passive"))
      (node (ref "U3") (pin "2") (pinfunction "PC13-TAMPER-RTC_2") (pintype "bidirectional"))
    )
    (net (code "49") (name "/pd2") (class "Default")
      (node (ref "U3") (pin "54") (pinfunction "PD2/TIM3_ETR/UART5_RX/SDIO_CMD_54") (pintype "bidirectional"))
    )
    (net (code "50") (name "/scl") (class "Default")
      (node (ref "P1") (pin "3") (pinfunction "3_3") (pintype "passive"))
      (node (ref "R35") (pin "2") (pinfunction "2_2") (pintype "passive"))
      (node (ref "U3") (pin "57") (pinfunction "PB5/TIM3_CH2/SPI1_MOSI/_57") (pintype "bidirectional"))
    )
    (net (code "51") (name "/sda") (class "Default")
      (node (ref "P1") (pin "4") (pinfunction "4_4") (pintype "passive"))
      (node (ref "R37") (pin "2") (pinfunction "2_2") (pintype "passive"))
      (node (ref "U3") (pin "59") (pinfunction "PB7/I2C1_SDA/FSMC_NADV/TIM4_CH2/USART1_RX_59") (pintype "bidirectional"))
    )
    (net (code "52") (name "GND") (class "Default")
      (node (ref "1") (pin "2") (pinfunction "2_2") (pintype "passive"))
      (node (ref "10") (pin "2") (pinfunction "2_2") (pintype "passive"))
      (node (ref "12") (pin "2") (pinfunction "2_2") (pintype "passive"))
      (node (ref "13") (pin "2") (pinfunction "2_2") (pintype "passive"))
      (node (ref "14") (pin "2") (pinfunction "2_2") (pintype "passive"))
      (node (ref "16") (pin "1") (pinfunction "1_1") (pintype "passive"))
      (node (ref "17") (pin "1") (pinfunction "1_1") (pintype "passive"))
      (node (ref "2") (pin "2") (pinfunction "2_2") (pintype "passive"))
      (node (ref "4") (pin "2") (pinfunction "2_2") (pintype "passive"))
      (node (ref "5") (pin "1") (pinfunction "1_1") (pintype "passive"))
      (node (ref "6") (pin "3") (pinfunction "GROUND_3") (pintype "power_in"))
      (node (ref "6") (pin "5") (pinfunction "~{ON}/OFF_5") (pintype "input"))
      (node (ref "6") (pin "6") (pinfunction "GND_TAB_6") (pintype "power_in"))
      (node (ref "7") (pin "2") (pinfunction "2_2") (pintype "passive"))
      (node (ref "8") (pin "1") (pinfunction "1_1") (pintype "passive"))
      (node (ref "9") (pin "5") (pinfunction "GND_5") (pintype "bidirectional"))
      (node (ref "BC1") (pin "2") (pinfunction "E_2") (pintype "passive"))
      (node (ref "BC11") (pin "2") (pinfunction "E_2") (pintype "passive"))
      (node (ref "BC12") (pin "2") (pinfunction "E_2") (pintype "passive"))
      (node (ref "BC13") (pin "2") (pinfunction "E_2") (pintype "passive"))
      (node (ref "BC2") (pin "2") (pinfunction "E_2") (pintype "passive"))
      (node (ref "BC3") (pin "2") (pinfunction "E_2") (pintype "passive"))
      (node (ref "BC4") (pin "2") (pinfunction "E_2") (pintype "passive"))
      (node (ref "BC5") (pin "2") (pinfunction "E_2") (pintype "passive"))
      (node (ref "BC8") (pin "2") (pinfunction "E_2") (pintype "passive"))
      (node (ref "BC9") (pin "2") (pinfunction "E_2") (pintype "passive"))
      (node (ref "C1") (pin "2") (pinfunction "2_2") (pintype "passive"))
      (node (ref "DZ1") (pin "1") (pintype "passive"))
      (node (ref "DZ2") (pin "1") (pintype "passive"))
      (node (ref "DZ3") (pin "1") (pintype "passive"))
      (node (ref "In+1") (pin "2") (pinfunction "2_2") (pintype "passive"))
      (node (ref "P1") (pin "2") (pinfunction "2_2") (pintype "passive"))
      (node (ref "P3") (pin "2") (pinfunction "2_2") (pintype "passive"))
      (node (ref "P5") (pin "4") (pinfunction "4_4") (pintype "passive"))
      (node (ref "Q1") (pin "3") (pinfunction "S_3") (pintype "passive"))
      (node (ref "R1") (pin "1") (pinfunction "1_1") (pintype "passive"))
      (node (ref "R22") (pin "1") (pinfunction "1_1") (pintype "passive"))
      (node (ref "R23") (pin "2") (pinfunction "2_2") (pintype "passive"))
      (node (ref "R25") (pin "1") (pinfunction "1_1") (pintype "passive"))
      (node (ref "R32") (pin "2") (pinfunction "2_2") (pintype "passive"))
      (node (ref "R34") (pin "1") (pinfunction "1_1") (pintype "passive"))
      (node (ref "R7") (pin "2") (pinfunction "2_2") (pintype "passive"))
      (node (ref "R8") (pin "2") (pinfunction "2_2") (pintype "passive"))
      (node (ref "U1") (pin "2") (pinfunction "1IN-_2") (pintype "input"))
      (node (ref "U1") (pin "4") (pinfunction "GND_4") (pintype "power_in"))
      (node (ref "U2") (pin "4") (pinfunction "GND_4") (pintype "power_in"))
      (node (ref "U2") (pin "5") (pinfunction "GND_5") (pintype "power_in"))
      (node (ref "U3") (pin "12") (pinfunction "VSSA_12") (pintype "power_in"))
      (node (ref "U3") (pin "18") (pinfunction "VSS_4_18") (pintype "power_in"))
      (node (ref "U3") (pin "31") (pinfunction "VSS_1_31") (pintype "power_in"))
      (node (ref "U3") (pin "47") (pinfunction "VSS_2_47") (pintype "power_in"))
      (node (ref "U3") (pin "60") (pinfunction "BOOT0_60") (pintype "input"))
      (node (ref "U3") (pin "63") (pinfunction "VSS_3_63") (pintype "power_in"))
      (node (ref "ams1") (pin "1") (pinfunction "GND_1") (pintype "power_in"))
      (node (ref "ca1") (pin "1") (pinfunction "1_1") (pintype "passive"))
      (node (ref "ca2") (pin "1") (pinfunction "1_1") (pintype "passive"))
      (node (ref "cc1") (pin "1") (pinfunction "1_1") (pintype "passive"))
      (node (ref "cr") (pin "2") (pinfunction "2_2") (pintype "passive"))
      (node (ref "rele4") (pin "2") (pinfunction "NC_2") (pintype "passive"))
      (node (ref "ss1") (pin "1") (pintype "passive"))
      (node (ref "uart") (pin "2") (pinfunction "2_2") (pintype "passive"))
    )
    (net (code "53") (name "Net-(6-OUTPUT)") (class "Default")
      (node (ref "3") (pin "1") (pinfunction "1_1") (pintype "passive"))
      (node (ref "6") (pin "2") (pinfunction "OUTPUT_2") (pintype "output"))
      (node (ref "ss1") (pin "2") (pintype "passive"))
    )
    (net (code "54") (name "Net-(9-FILTER)") (class "Default")
      (node (ref "9") (pin "6") (pinfunction "FILTER_6") (pintype "bidirectional"))
      (node (ref "ca1") (pin "2") (pinfunction "2_2") (pintype "passive"))
    )
    (net (code "55") (name "Net-(9-IP+)") (class "Default")
      (node (ref "9") (pin "1") (pinfunction "IP+_1") (pintype "bidirectional"))
      (node (ref "9") (pin "2") (pinfunction "IP+@1_2") (pintype "bidirectional"))
      (node (ref "pinIN1") (pin "1") (pinfunction "1_1") (pintype "passive"))
    )
    (net (code "56") (name "Net-(9-IP-)") (class "Default")
      (node (ref "9") (pin "3") (pinfunction "IP-_3") (pintype "bidirectional"))
      (node (ref "9") (pin "4") (pinfunction "IP-@1_4") (pintype "bidirectional"))
      (node (ref "rele1") (pin "1") (pinfunction "COM_1") (pintype "passive"))
    )
    (net (code "57") (name "Net-(BC1-B)") (class "Default")
      (node (ref "BC1") (pin "1") (pinfunction "B_1") (pintype "passive"))
      (node (ref "R3") (pin "1") (pinfunction "1_1") (pintype "passive"))
      (node (ref "R7") (pin "1") (pinfunction "1_1") (pintype "passive"))
    )
    (net (code "58") (name "Net-(BC2-B)") (class "Default")
      (node (ref "BC2") (pin "1") (pinfunction "B_1") (pintype "passive"))
      (node (ref "R11") (pin "1") (pinfunction "1_1") (pintype "passive"))
    )
    (net (code "59") (name "Net-(BC2-C)") (class "Default")
      (node (ref "BC2") (pin "3") (pinfunction "C_3") (pintype "passive"))
      (node (ref "D2") (pin "1") (pintype "passive"))
      (node (ref "rele1") (pin "4") (pinfunction "T1_4") (pintype "passive"))
      (node (ref "rele2") (pin "4") (pinfunction "T1_4") (pintype "passive"))
    )
    (net (code "60") (name "Net-(BC3-B)") (class "Default")
      (node (ref "BC3") (pin "1") (pinfunction "B_1") (pintype "passive"))
      (node (ref "R12") (pin "1") (pinfunction "1_1") (pintype "passive"))
    )
    (net (code "61") (name "Net-(BC3-C)") (class "Default")
      (node (ref "BC3") (pin "3") (pinfunction "C_3") (pintype "passive"))
      (node (ref "D3") (pin "1") (pintype "passive"))
      (node (ref "rele3") (pin "4") (pinfunction "T1_4") (pintype "passive"))
      (node (ref "rele4") (pin "4") (pinfunction "T1_4") (pintype "passive"))
    )
    (net (code "62") (name "Net-(BC4-B)") (class "Default")
      (node (ref "BC4") (pin "1") (pinfunction "B_1") (pintype "passive"))
      (node (ref "R13") (pin "1") (pinfunction "1_1") (pintype "passive"))
    )
    (net (code "63") (name "Net-(BC4-C)") (class "Default")
      (node (ref "BC4") (pin "3") (pinfunction "C_3") (pintype "passive"))
      (node (ref "D4") (pin "1") (pintype "passive"))
      (node (ref "rele5") (pin "5") (pinfunction "T2_5") (pintype "passive"))
    )
    (net (code "64") (name "Net-(BC5-B)") (class "Default")
      (node (ref "BC5") (pin "1") (pinfunction "B_1") (pintype "passive"))
      (node (ref "R14") (pin "1") (pinfunction "1_1") (pintype "passive"))
    )
    (net (code "65") (name "Net-(BC5-C)") (class "Default")
      (node (ref "BC5") (pin "3") (pinfunction "C_3") (pintype "passive"))
      (node (ref "D5") (pin "1") (pintype "passive"))
      (node (ref "rele6") (pin "4") (pinfunction "T1_4") (pintype "passive"))
    )
    (net (code "66") (name "Net-(BC7-B)") (class "Default")
      (node (ref "BC7") (pin "1") (pinfunction "B_1") (pintype "passive"))
      (node (ref "R16") (pin "1") (pinfunction "1_1") (pintype "passive"))
      (node (ref "R20") (pin "2") (pinfunction "2_2") (pintype "passive"))
    )
    (net (code "67") (name "Net-(BC7-C)") (class "Default")
      (node (ref "BC7") (pin "3") (pinfunction "C_3") (pintype "passive"))
      (node (ref "Q1") (pin "1") (pinfunction "G_1") (pintype "passive"))
      (node (ref "R25") (pin "2") (pinfunction "2_2") (pintype "passive"))
    )
    (net (code "68") (name "Net-(BC8-B)") (class "Default")
      (node (ref "BC8") (pin "1") (pinfunction "B_1") (pintype "passive"))
      (node (ref "R19") (pin "2") (pinfunction "2_2") (pintype "passive"))
    )
    (net (code "69") (name "Net-(BC8-C)") (class "Default")
      (node (ref "BC8") (pin "3") (pinfunction "C_3") (pintype "passive"))
      (node (ref "D7") (pin "1") (pintype "passive"))
      (node (ref "rele8") (pin "4") (pinfunction "T1_4") (pintype "passive"))
    )
    (net (code "70") (name "Net-(BC9-B)") (class "Default")
      (node (ref "BC9") (pin "1") (pinfunction "B_1") (pintype "passive"))
      (node (ref "re1") (pin "1") (pinfunction "1_1") (pintype "passive"))
    )
    (net (code "71") (name "Net-(BC9-C)") (class "Default")
      (node (ref "BC9") (pin "3") (pinfunction "C_3") (pintype "passive"))
      (node (ref "CO") (pin "2") (pinfunction "-_2") (pintype "passive"))
    )
    (net (code "72") (name "Net-(BC10-B)") (class "Default")
      (node (ref "BC10") (pin "1") (pinfunction "B_1") (pintype "passive"))
      (node (ref "R18") (pin "2") (pinfunction "2_2") (pintype "passive"))
      (node (ref "R26") (pin "1") (pinfunction "1_1") (pintype "passive"))
    )
    (net (code "73") (name "Net-(BC10-C)") (class "Default")
      (node (ref "BC10") (pin "3") (pinfunction "C_3") (pintype "passive"))
      (node (ref "R31") (pin "1") (pinfunction "1_1") (pintype "passive"))
    )
    (net (code "74") (name "Net-(BC11-B)") (class "Default")
      (node (ref "BC11") (pin "1") (pinfunction "B_1") (pintype "passive"))
      (node (ref "R27") (pin "2") (pinfunction "2_2") (pintype "passive"))
    )
    (net (code "75") (name "Net-(BC11-C)") (class "Default")
      (node (ref "BC11") (pin "3") (pinfunction "C_3") (pintype "passive"))
      (node (ref "R20") (pin "1") (pinfunction "1_1") (pintype "passive"))
    )
    (net (code "76") (name "Net-(BC12-B)") (class "Default")
      (node (ref "BC12") (pin "1") (pinfunction "B_1") (pintype "passive"))
      (node (ref "R30") (pin "1") (pinfunction "1_1") (pintype "passive"))
    )
    (net (code "77") (name "Net-(BC12-C)") (class "Default")
      (node (ref "BC12") (pin "3") (pinfunction "C_3") (pintype "passive"))
      (node (ref "R26") (pin "2") (pinfunction "2_2") (pintype "passive"))
    )
    (net (code "78") (name "Net-(BC13-B)") (class "Default")
      (node (ref "BC13") (pin "1") (pinfunction "B_1") (pintype "passive"))
      (node (ref "R36") (pin "2") (pinfunction "2_2") (pintype "passive"))
    )
    (net (code "79") (name "Net-(BC13-C)") (class "Default")
      (node (ref "BC13") (pin "3") (pinfunction "C_3") (pintype "passive"))
      (node (ref "Buzzer1") (pin "2") (pinfunction "-_2") (pintype "passive"))
    )
    (net (code "80") (name "Net-(D1-K)") (class "Default")
      (node (ref "D1") (pin "C") (pinfunction "K_C") (pintype "passive"))
      (node (ref "DZ3") (pin "2") (pintype "passive"))
      (node (ref "R9") (pin "1") (pinfunction "1_1") (pintype "passive"))
    )
    (net (code "81") (name "Net-(Din1-Pad1)") (class "Default")
      (node (ref "Din1") (pin "1") (pintype "passive"))
      (node (ref "Inbutton1") (pin "1") (pinfunction "1_1") (pintype "passive"))
    )
    (net (code "82") (name "Net-(In+1-Pad1)") (class "Default")
      (node (ref "In+1") (pin "1") (pinfunction "1_1") (pintype "passive"))
      (node (ref "Inbutton1") (pin "2") (pinfunction "2_2") (pintype "passive"))
    )
    (net (code "83") (name "Net-(P1-Pad7)") (class "Default")
      (node (ref "P1") (pin "7") (pinfunction "7_7") (pintype "passive"))
      (node (ref "R21") (pin "2") (pinfunction "2_2") (pintype "passive"))
    )
    (net (code "84") (name "Net-(U1-2IN+)") (class "Default")
      (node (ref "R6") (pin "1") (pinfunction "1_1") (pintype "passive"))
      (node (ref "R8") (pin "1") (pinfunction "1_1") (pintype "passive"))
      (node (ref "U1") (pin "5") (pinfunction "2IN+_5") (pintype "input"))
    )
    (net (code "85") (name "Net-(U1-2OUT)") (class "Default")
      (node (ref "R5") (pin "2") (pinfunction "2_2") (pintype "passive"))
      (node (ref "U1") (pin "7") (pinfunction "2OUT_7") (pintype "output"))
    )
    (net (code "86") (name "Net-(U2-INPUT)") (class "Default")
      (node (ref "R22") (pin "2") (pinfunction "2_2") (pintype "passive"))
      (node (ref "R31") (pin "2") (pinfunction "2_2") (pintype "passive"))
      (node (ref "U2") (pin "2") (pinfunction "INPUT_2") (pintype "input"))
    )
    (net (code "87") (name "Net-(U3-NRST)") (class "Default")
      (node (ref "U3") (pin "7") (pinfunction "NRST_7") (pintype "input"))
      (node (ref "cr") (pin "1") (pinfunction "1_1") (pintype "passive"))
      (node (ref "rr") (pin "2") (pinfunction "2_2") (pintype "passive"))
    )
    (net (code "88") (name "Net-(U3-PC2{slash}ADC123_IN12)") (class "Default")
      (node (ref "R33") (pin "1") (pinfunction "1_1") (pintype "passive"))
      (node (ref "R34") (pin "2") (pinfunction "2_2") (pintype "passive"))
      (node (ref "U3") (pin "10") (pinfunction "PC2/ADC123_IN12_10") (pintype "bidirectional"))
    )
    (net (code "89") (name "Net-(U3-PD0-OSC_IN{slash}FSMC_D2{slash}CAN_RX)") (class "Default")
      (node (ref "16") (pin "2") (pinfunction "2_2") (pintype "passive"))
      (node (ref "U3") (pin "5") (pinfunction "PD0-OSC_IN/FSMC_D2/CAN_RX_5") (pintype "bidirectional"))
      (node (ref "Y1") (pin "2") (pinfunction "2_2") (pintype "passive"))
    )
    (net (code "90") (name "Net-(U3-PD1-OSC_OUT{slash}FSMC_D3{slash}CAN_TX)") (class "Default")
      (node (ref "17") (pin "2") (pinfunction "2_2") (pintype "passive"))
      (node (ref "U3") (pin "6") (pinfunction "PD1-OSC_OUT/FSMC_D3/CAN_TX_6") (pintype "bidirectional"))
      (node (ref "Y1") (pin "1") (pinfunction "1_1") (pintype "passive"))
    )
    (net (code "91") (name "Net-(rele1-NC)") (class "Default")
      (node (ref "rele1") (pin "2") (pinfunction "NC_2") (pintype "passive"))
      (node (ref "rele3") (pin "1") (pinfunction "COM_1") (pintype "passive"))
    )
    (net (code "92") (name "Net-(rele1-NO)") (class "Default")
      (node (ref "rele1") (pin "3") (pinfunction "NO_3") (pintype "passive"))
      (node (ref "rele2") (pin "3") (pinfunction "NO_3") (pintype "passive"))
    )
    (net (code "93") (name "Net-(rele2-COM)") (class "Default")
      (node (ref "pinIN1") (pin "2") (pinfunction "2_2") (pintype "passive"))
      (node (ref "rele2") (pin "1") (pinfunction "COM_1") (pintype "passive"))
    )
    (net (code "94") (name "Net-(rele2-NC)") (class "Default")
      (node (ref "rele2") (pin "2") (pinfunction "NC_2") (pintype "passive"))
      (node (ref "rele4") (pin "1") (pinfunction "COM_1") (pintype "passive"))
    )
    (net (code "95") (name "Net-(rele3-NC)") (class "Default")
      (node (ref "rele3") (pin "2") (pinfunction "NC_2") (pintype "passive"))
      (node (ref "rele5") (pin "1") (pinfunction "COM_1") (pintype "passive"))
    )
    (net (code "96") (name "Net-(rele5-NO)") (class "Default")
      (node (ref "rele5") (pin "3") (pinfunction "NO_3") (pintype "passive"))
      (node (ref "rele6") (pin "1") (pinfunction "COM_1") (pintype "passive"))
    )
    (net (code "97") (name "Net-(rele8-COM)") (class "Default")
      (node (ref "L1") (pin "1") (pinfunction "1_1") (pintype "passive"))
      (node (ref "U2") (pin "6") (pinfunction "OUTPUT_6") (pintype "output"))
      (node (ref "U2") (pin "7") (pinfunction "OUTPUT_7") (pintype "output"))
      (node (ref "rele8") (pin "1") (pinfunction "COM_1") (pintype "passive"))
    )
    (net (code "98") (name "Net-(rele8-NC)") (class "Default")
      (node (ref "L1") (pin "2") (pinfunction "2_2") (pintype "passive"))
      (node (ref "R28") (pin "1") (pinfunction "1_1") (pintype "passive"))
      (node (ref "rele8") (pin "2") (pinfunction "NC_2") (pintype "passive"))
    )
    (net (code "99") (name "VCC") (class "Default")
      (node (ref "10") (pin "1") (pinfunction "1_1") (pintype "passive"))
      (node (ref "12") (pin "1") (pinfunction "1_1") (pintype "passive"))
      (node (ref "13") (pin "1") (pinfunction "1_1") (pintype "passive"))
      (node (ref "14") (pin "1") (pinfunction "1_1") (pintype "passive"))
      (node (ref "4") (pin "1") (pinfunction "1_1") (pintype "passive"))
      (node (ref "5") (pin "2") (pinfunction "2_2") (pintype "passive"))
      (node (ref "7") (pin "1") (pinfunction "1_1") (pintype "passive"))
      (node (ref "9") (pin "8") (pinfunction "VCC_8") (pintype "bidirectional"))
      (node (ref "P1") (pin "1") (pinfunction "1_1") (pintype "passive"))
      (node (ref "P3") (pin "1") (pinfunction "1_1") (pintype "passive"))
      (node (ref "R10") (pin "2") (pinfunction "2_2") (pintype "passive"))
      (node (ref "R2") (pin "2") (pinfunction "2_2") (pintype "passive"))
      (node (ref "R24") (pin "2") (pinfunction "2_2") (pintype "passive"))
      (node (ref "R35") (pin "1") (pinfunction "1_1") (pintype "passive"))
      (node (ref "R37") (pin "1") (pinfunction "1_1") (pintype "passive"))
      (node (ref "R6") (pin "2") (pinfunction "2_2") (pintype "passive"))
      (node (ref "U1") (pin "8") (pinfunction "VCC_8") (pintype "power_in"))
      (node (ref "U3") (pin "13") (pinfunction "VDDA_13") (pintype "power_in"))
      (node (ref "U3") (pin "19") (pinfunction "VDD_4_19") (pintype "power_in"))
      (node (ref "U3") (pin "32") (pinfunction "VDD_1_32") (pintype "power_in"))
      (node (ref "U3") (pin "48") (pinfunction "VDD_2_48") (pintype "power_in"))
      (node (ref "U3") (pin "64") (pinfunction "VDD_3_64") (pintype "power_in"))
      (node (ref "ams1") (pin "2") (pinfunction "OUT_2") (pintype "power_in"))
      (node (ref "ams1") (pin "4") (pinfunction "TAB_4") (pintype "power_in"))
      (node (ref "ca2") (pin "2") (pinfunction "2_2") (pintype "passive"))
      (node (ref "cc1") (pin "2") (pinfunction "2_2") (pintype "passive"))
      (node (ref "rr") (pin "1") (pinfunction "1_1") (pintype "passive"))
    )
    (net (code "100") (name "unconnected-(P1-Pad5)") (class "Default")
      (node (ref "P1") (pin "5") (pinfunction "5_5") (pintype "passive"))
    )
    (net (code "101") (name "unconnected-(P1-Pad6)") (class "Default")
      (node (ref "P1") (pin "6") (pinfunction "6_6") (pintype "passive"))
    )
    (net (code "102") (name "unconnected-(P1-Pad8)") (class "Default")
      (node (ref "P1") (pin "8") (pinfunction "8_8") (pintype "passive"))
    )
    (net (code "103") (name "unconnected-(P1-Pad9)") (class "Default")
      (node (ref "P1") (pin "9") (pinfunction "9_9") (pintype "passive"))
    )
    (net (code "104") (name "unconnected-(P1-Pad10)") (class "Default")
      (node (ref "P1") (pin "10") (pinfunction "10_10") (pintype "passive"))
    )
    (net (code "105") (name "unconnected-(P3-Pad6)") (class "Default")
      (node (ref "P3") (pin "6") (pinfunction "6_6") (pintype "passive+no_connect"))
    )
    (net (code "106") (name "unconnected-(P3-Pad9)") (class "Default")
      (node (ref "P3") (pin "9") (pinfunction "9_9") (pintype "passive+no_connect"))
    )
    (net (code "107") (name "unconnected-(U1-1OUT-Pad1)") (class "Default")
      (node (ref "U1") (pin "1") (pinfunction "1OUT_1") (pintype "output"))
    )
    (net (code "108") (name "unconnected-(U2-NC-Pad3)") (class "Default")
      (node (ref "U2") (pin "3") (pinfunction "NC_3") (pintype "bidirectional"))
    )
    (net (code "109") (name "unconnected-(U3-PB2{slash}{slash}BOOT1-Pad28)") (class "Default")
      (node (ref "U3") (pin "28") (pinfunction "PB2//BOOT1_28") (pintype "bidirectional+no_connect"))
    )
    (net (code "110") (name "unconnected-(U3-PB3{slash}SPI3_SCK{slash}I2S3_CK{slash}TRACESWO{slash}TIM2_CH2{slash}SPI1_SCK-Pad55)") (class "Default")
      (node (ref "U3") (pin "55") (pinfunction "PB3/SPI3_SCK/I2S3_CK/TRACESWO/TIM2_CH2/SPI1_SCK_55") (pintype "bidirectional+no_connect"))
    )
    (net (code "111") (name "unconnected-(U3-PB4{slash}SPI3_MISO{slash}TIM3_CH1{slash}SPI1_MISO-Pad56)") (class "Default")
      (node (ref "U3") (pin "56") (pinfunction "PB4/SPI3_MISO/TIM3_CH1/SPI1_MISO_56") (pintype "bidirectional+no_connect"))
    )
    (net (code "112") (name "unconnected-(U3-VBAT-Pad1)") (class "Default")
      (node (ref "U3") (pin "1") (pinfunction "VBAT_1") (pintype "power_in"))
    )
    (net (code "113") (name "unconnected-(rele8-NO-Pad3)") (class "Default")
      (node (ref "rele8") (pin "3") (pinfunction "NO_3") (pintype "passive"))
    )
  )
)
